# SOCL_506_GINDRING.net
KiCad netlist of a schematic drawn in EAGLE
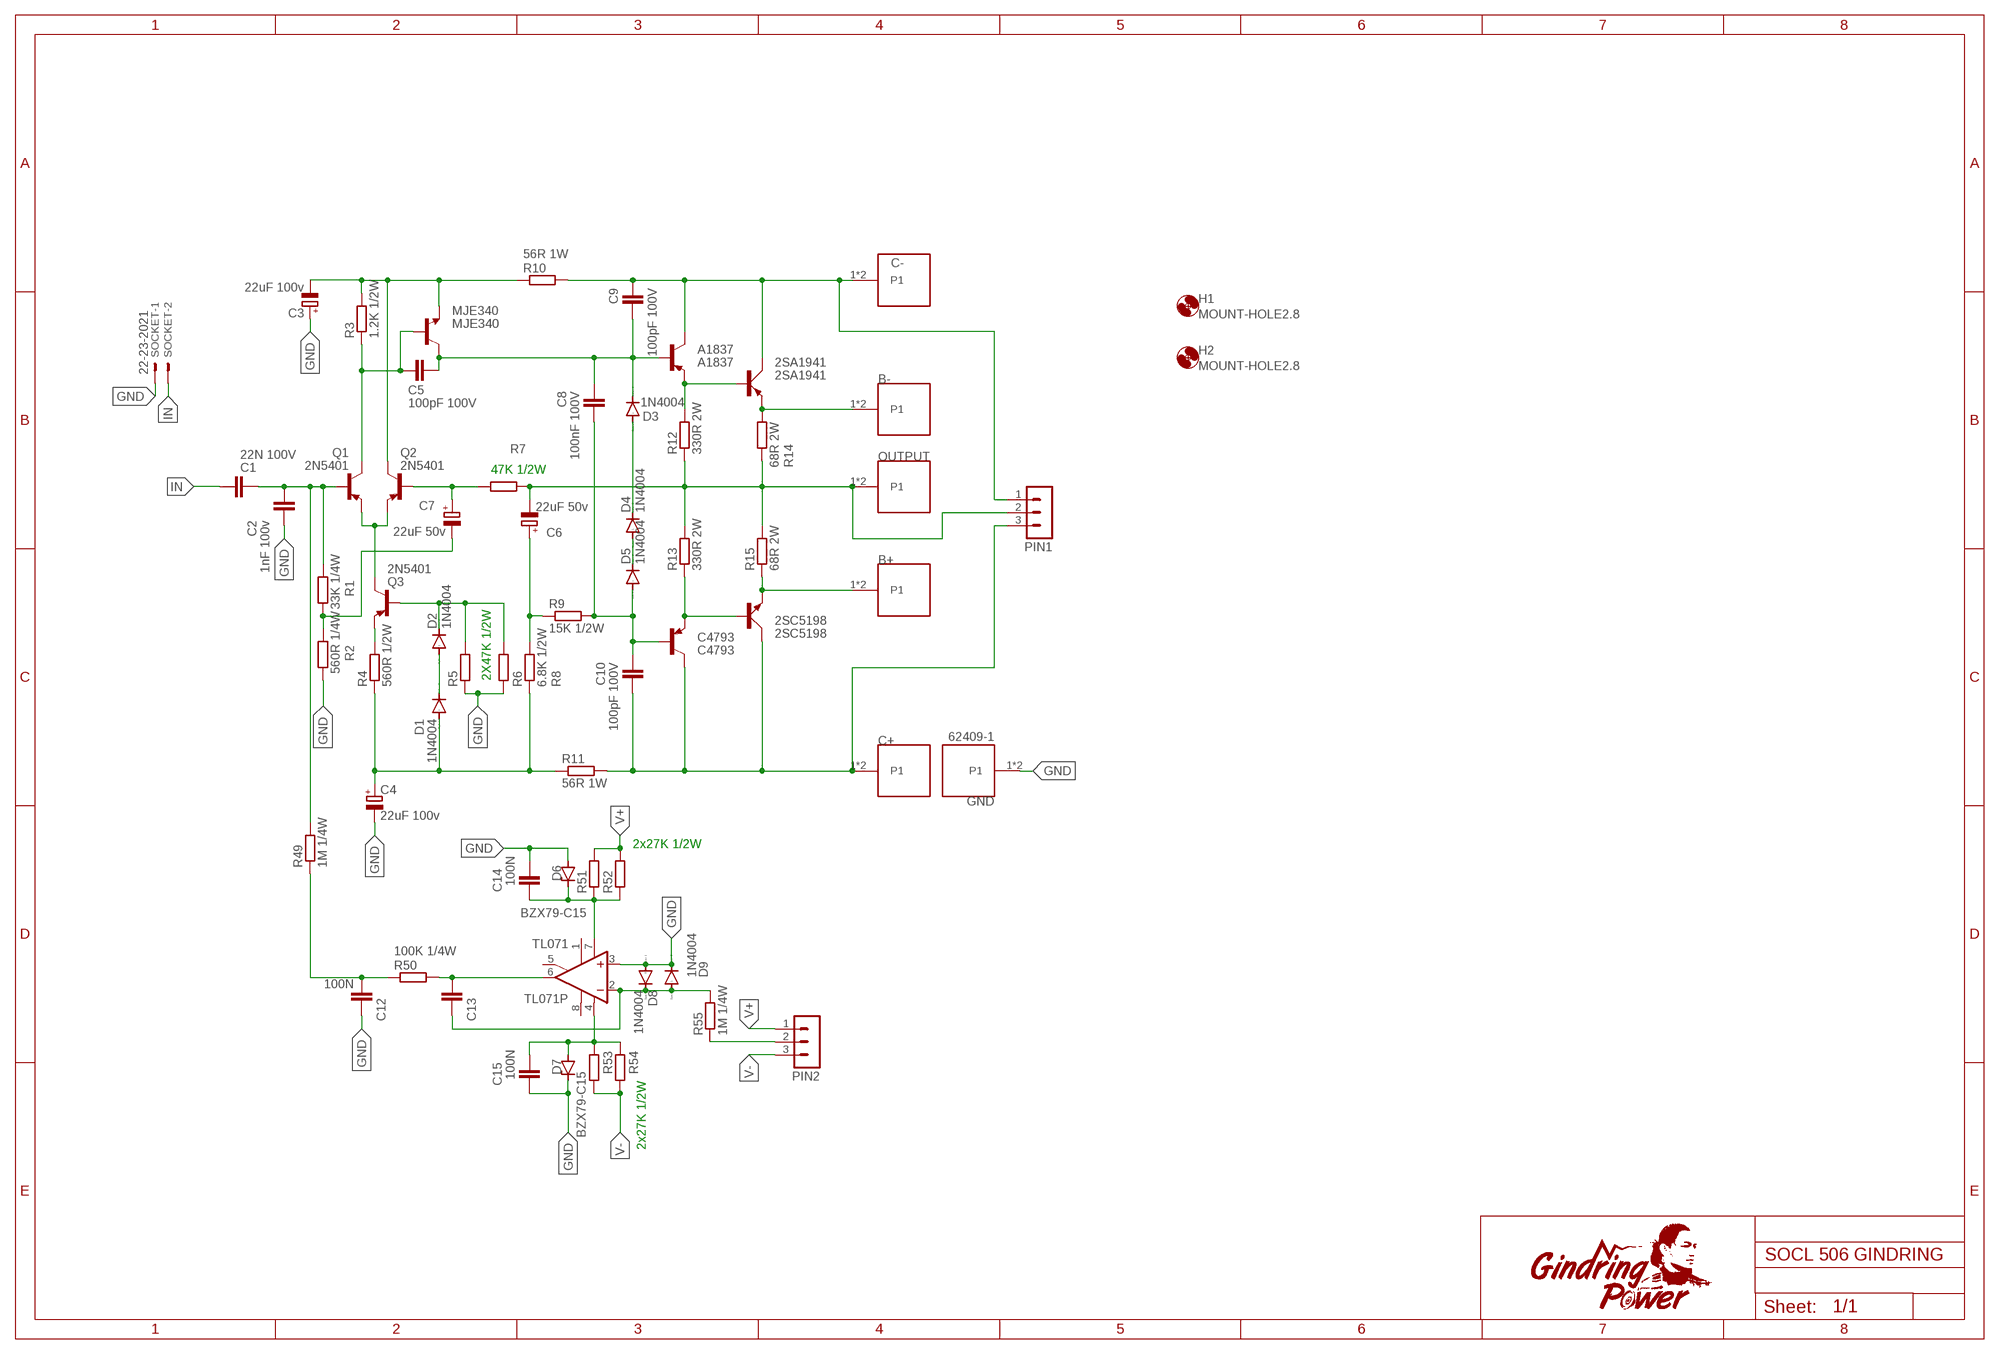
[diagram p0: schematic, sheet 1]

(export (version "E")
  (design (tool "Eeschema 10.0.6"))
  (components
    (comp (ref "2SA1941")
      (value "2SA1941")
      (footprint "eagle-import:TOP3AV")
      (libsource (lib "eagle-import") (part "TIP2955"))
    )
    (comp (ref "2SC5198")
      (value "2SC5198")
      (footprint "eagle-import:TOP3AV")
      (libsource (lib "eagle-import") (part "TIP3055"))
    )
    (comp (ref "A1837")
      (value "A1837")
      (footprint "eagle-import:TO220V")
      (fields (field (name "MF") "Toshiba Semiconductor") (field (name "MP") "2SA1837"))
      (libsource (lib "eagle-import") (part "2SA1837"))
    )
    (comp (ref "B+")
      (value "62409-1")
      (footprint "eagle-import:TE_62409-1")
      (fields (field (name "MF") "TE Connectivity"))
      (libsource (lib "eagle-import") (part "62409-1"))
    )
    (comp (ref "B-")
      (value "62409-1")
      (footprint "eagle-import:TE_62409-1")
      (fields (field (name "MF") "TE Connectivity"))
      (libsource (lib "eagle-import") (part "62409-1"))
    )
    (comp (ref "C+")
      (value "62409-1")
      (footprint "eagle-import:TE_62409-1")
      (fields (field (name "MF") "TE Connectivity"))
      (libsource (lib "eagle-import") (part "62409-1"))
    )
    (comp (ref "C-")
      (value "62409-1")
      (footprint "eagle-import:TE_62409-1")
      (fields (field (name "MF") "TE Connectivity"))
      (libsource (lib "eagle-import") (part "62409-1"))
    )
    (comp (ref "C1")
      (value "22N 100V")
      (footprint "eagle-import:C5B2.5")
      (libsource (lib "eagle-import") (part "C5/2.5"))
    )
    (comp (ref "C2")
      (value "1nF 100v")
      (footprint "eagle-import:C5B2.5")
      (libsource (lib "eagle-import") (part "C5/2.5"))
    )
    (comp (ref "C3")
      (value "22uF 100v")
      (footprint "eagle-import:E3,5-8")
      (libsource (lib "eagle-import") (part "CPOL-EUE3.5-8"))
    )
    (comp (ref "C4")
      (value "22uF 100v")
      (footprint "eagle-import:E3,5-8")
      (libsource (lib "eagle-import") (part "CPOL-EUE3.5-8"))
    )
    (comp (ref "C5")
      (value "100pF 100V")
      (footprint "eagle-import:C5B2.5")
      (libsource (lib "eagle-import") (part "C5/2.5"))
    )
    (comp (ref "C6")
      (value "22uF 50v")
      (footprint "eagle-import:E2,5-6E")
      (libsource (lib "eagle-import") (part "CPOL-EUE2,5-6E"))
    )
    (comp (ref "C7")
      (value "22uF 50v")
      (footprint "eagle-import:E2,5-6E")
      (libsource (lib "eagle-import") (part "CPOL-EUE2,5-6E"))
    )
    (comp (ref "C8")
      (value "100nF 100V")
      (footprint "eagle-import:C5B2.5")
      (libsource (lib "eagle-import") (part "C5/2.5"))
    )
    (comp (ref "C9")
      (value "100pF 100V")
      (footprint "eagle-import:C5B2.5")
      (libsource (lib "eagle-import") (part "C5/2.5"))
    )
    (comp (ref "C10")
      (value "100pF 100V")
      (footprint "eagle-import:C5B2.5")
      (libsource (lib "eagle-import") (part "C5/2.5"))
    )
    (comp (ref "C12")
      (value "100N")
      (footprint "eagle-import:C5B2.5")
      (libsource (lib "eagle-import") (part "C5/2.5"))
    )
    (comp (ref "C13")
      (value "100N")
      (footprint "eagle-import:C5B2.5")
      (libsource (lib "eagle-import") (part "C5/2.5"))
    )
    (comp (ref "C14")
      (value "100N")
      (footprint "eagle-import:C5B2.5")
      (libsource (lib "eagle-import") (part "C5/2.5"))
    )
    (comp (ref "C15")
      (value "100N")
      (footprint "eagle-import:C5B2.5")
      (libsource (lib "eagle-import") (part "C5/2.5"))
    )
    (comp (ref "C4793")
      (value "C4793")
      (footprint "eagle-import:TO220V")
      (fields (field (name "MF") "Toshiba Semiconductor") (field (name "MP") "2SA1837"))
      (libsource (lib "eagle-import") (part "2SA1837"))
    )
    (comp (ref "D1")
      (value "1N4004")
      (footprint "eagle-import:DO41-10")
      (libsource (lib "eagle-import") (part "1N4004"))
    )
    (comp (ref "D2")
      (value "1N4004")
      (footprint "eagle-import:DO41-10")
      (libsource (lib "eagle-import") (part "1N4004"))
    )
    (comp (ref "D3")
      (value "1N4004")
      (footprint "eagle-import:DO41-10")
      (libsource (lib "eagle-import") (part "1N4004"))
    )
    (comp (ref "D4")
      (value "1N4004")
      (footprint "eagle-import:DO41-10")
      (libsource (lib "eagle-import") (part "1N4004"))
    )
    (comp (ref "D5")
      (value "1N4004")
      (footprint "eagle-import:DO41-10")
      (libsource (lib "eagle-import") (part "1N4004"))
    )
    (comp (ref "D6")
      (value "BZX79-C15")
      (footprint "eagle-import:DO41Z10")
      (libsource (lib "eagle-import") (part "1N4728"))
    )
    (comp (ref "D7")
      (value "BZX79-C15")
      (footprint "eagle-import:DO41Z10")
      (libsource (lib "eagle-import") (part "1N4728"))
    )
    (comp (ref "D8")
      (value "1N4004")
      (footprint "eagle-import:DO41-10")
      (libsource (lib "eagle-import") (part "1N4004"))
    )
    (comp (ref "D9")
      (value "1N4004")
      (footprint "eagle-import:DO41-10")
      (libsource (lib "eagle-import") (part "1N4004"))
    )
    (comp (ref "GND")
      (value "62409-1")
      (footprint "eagle-import:TE_62409-1")
      (fields (field (name "MF") "TE Connectivity"))
      (libsource (lib "eagle-import") (part "62409-1"))
    )
    (comp (ref "H1")
      (value "MOUNT-HOLE2.8")
      (footprint "eagle-import:2,8")
      (libsource (lib "eagle-import") (part "MOUNT-HOLE2.8"))
    )
    (comp (ref "H2")
      (value "MOUNT-HOLE2.8")
      (footprint "eagle-import:2,8")
      (libsource (lib "eagle-import") (part "MOUNT-HOLE2.8"))
    )
    (comp (ref "MJE340")
      (value "MJE340")
      (footprint "eagle-import:TO126")
      (fields (field (name "MF") "STMicroelectronics"))
      (libsource (lib "eagle-import") (part "MJE340"))
    )
    (comp (ref "OUTPUT")
      (value "62409-1")
      (footprint "eagle-import:TE_62409-1")
      (fields (field (name "MF") "TE Connectivity"))
      (libsource (lib "eagle-import") (part "62409-1"))
    )
    (comp (ref "PIN1")
      (value "MA03-1")
      (footprint "eagle-import:MA03-1")
      (libsource (lib "eagle-import") (part "MA03-1"))
    )
    (comp (ref "PIN2")
      (value "MA03-1")
      (footprint "eagle-import:MA03-1")
      (libsource (lib "eagle-import") (part "MA03-1"))
    )
    (comp (ref "Q1")
      (value "2N5401")
      (footprint "eagle-import:TO92-CBE")
      (libsource (lib "eagle-import") (part "-?TO92MPSA56"))
    )
    (comp (ref "Q2")
      (value "2N5401")
      (footprint "eagle-import:TO92-CBE")
      (libsource (lib "eagle-import") (part "-?TO92MPSA56"))
    )
    (comp (ref "Q3")
      (value "2N5401")
      (footprint "eagle-import:TO92-CBE")
      (libsource (lib "eagle-import") (part "-?TO92MPSA56"))
    )
    (comp (ref "R1")
      (value "33K 1/4W")
      (footprint "eagle-import:0207_10")
      (libsource (lib "eagle-import") (part "R-EU_0207/10"))
    )
    (comp (ref "R2")
      (value "560R 1/4W")
      (footprint "eagle-import:0207_10")
      (libsource (lib "eagle-import") (part "R-EU_0207/10"))
    )
    (comp (ref "R3")
      (value "1.2K 1/2W")
      (footprint "eagle-import:0207_15")
      (libsource (lib "eagle-import") (part "resistor coba_R-EU_0207/15"))
    )
    (comp (ref "R4")
      (value "560R 1/2W")
      (footprint "eagle-import:0207_15")
      (libsource (lib "eagle-import") (part "resistor coba_R-EU_0207/15"))
    )
    (comp (ref "R5")
      (value "R-EU_0207/15")
      (footprint "eagle-import:0207_15")
      (libsource (lib "eagle-import") (part "resistor coba_R-EU_0207/15"))
    )
    (comp (ref "R6")
      (value "R-EU_0207/15")
      (footprint "eagle-import:0207_15")
      (libsource (lib "eagle-import") (part "resistor coba_R-EU_0207/15"))
    )
    (comp (ref "R7")
      (value "R-EU_0207/15")
      (footprint "eagle-import:0207_15")
      (libsource (lib "eagle-import") (part "resistor coba_R-EU_0207/15"))
    )
    (comp (ref "R8")
      (value "6.8K 1/2W")
      (footprint "eagle-import:0207_15")
      (libsource (lib "eagle-import") (part "resistor coba_R-EU_0207/15"))
    )
    (comp (ref "R9")
      (value "15K 1/2W")
      (footprint "eagle-import:0207_15")
      (libsource (lib "eagle-import") (part "resistor coba_R-EU_0207/15"))
    )
    (comp (ref "R10")
      (value "56R 1W")
      (footprint "eagle-import:0207_15")
      (libsource (lib "eagle-import") (part "resistor coba_R-EU_0207/15"))
    )
    (comp (ref "R11")
      (value "56R 1W")
      (footprint "eagle-import:0207_15")
      (libsource (lib "eagle-import") (part "resistor coba_R-EU_0207/15"))
    )
    (comp (ref "R12")
      (value "330R 2W")
      (footprint "eagle-import:0207_15")
      (libsource (lib "eagle-import") (part "resistor coba_R-EU_0207/15"))
    )
    (comp (ref "R13")
      (value "330R 2W")
      (footprint "eagle-import:0207_15")
      (libsource (lib "eagle-import") (part "resistor coba_R-EU_0207/15"))
    )
    (comp (ref "R14")
      (value "68R 2W")
      (footprint "eagle-import:0207_15")
      (libsource (lib "eagle-import") (part "resistor coba_R-EU_0207/15"))
    )
    (comp (ref "R15")
      (value "68R 2W")
      (footprint "eagle-import:0207_15")
      (libsource (lib "eagle-import") (part "resistor coba_R-EU_0207/15"))
    )
    (comp (ref "R49")
      (value "1M 1/4W")
      (footprint "eagle-import:0207_10")
      (libsource (lib "eagle-import") (part "R-EU_0207/10"))
    )
    (comp (ref "R50")
      (value "100K 1/4W")
      (footprint "eagle-import:0207_10")
      (libsource (lib "eagle-import") (part "R-EU_0207/10"))
    )
    (comp (ref "R51")
      (value "R-EU_0207/15")
      (footprint "eagle-import:0207_15")
      (libsource (lib "eagle-import") (part "resistor coba_R-EU_0207/15"))
    )
    (comp (ref "R52")
      (value "R-EU_0207/15")
      (footprint "eagle-import:0207_15")
      (libsource (lib "eagle-import") (part "resistor coba_R-EU_0207/15"))
    )
    (comp (ref "R53")
      (value "R-EU_0207/15")
      (footprint "eagle-import:0207_15")
      (libsource (lib "eagle-import") (part "resistor coba_R-EU_0207/15"))
    )
    (comp (ref "R54")
      (value "R-EU_0207/15")
      (footprint "eagle-import:0207_15")
      (libsource (lib "eagle-import") (part "resistor coba_R-EU_0207/15"))
    )
    (comp (ref "R55")
      (value "1M 1/4W")
      (footprint "eagle-import:0207_10")
      (libsource (lib "eagle-import") (part "R-EU_0207/10"))
    )
    (comp (ref "SOCKET")
      (value "22-23-2021")
      (footprint "eagle-import:22-23-2021")
      (fields (field (name "MF") "MOLEX"))
      (libsource (lib "eagle-import") (part "22-23-2021"))
    )
    (comp (ref "TL071")
      (value "TL071P")
      (footprint "eagle-import:DIL08")
      (fields (field (name "MF") "STMicroelectronics") (field (name "MP") "TL071"))
      (libsource (lib "eagle-import") (part "TL071P"))
    )
  )
  (nets
    (net (code "1") (name "GND") (class "Default")
      (node (ref "C12") (pin "1") (pinfunction "1_1") (pintype "passive"))
      (node (ref "C14") (pin "2") (pinfunction "2_2") (pintype "passive"))
      (node (ref "C15") (pin "1") (pinfunction "1_1") (pintype "passive"))
      (node (ref "C2") (pin "2") (pinfunction "2_2") (pintype "passive"))
      (node (ref "C3") (pin "+") (pinfunction "+_+") (pintype "passive"))
      (node (ref "C4") (pin "-") (pinfunction "-_-") (pintype "passive"))
      (node (ref "D6") (pin "A") (pinfunction "A_A") (pintype "passive"))
      (node (ref "D7") (pin "C") (pinfunction "C_C") (pintype "passive"))
      (node (ref "D8") (pin "A") (pinfunction "A_A") (pintype "passive"))
      (node (ref "D9") (pin "C") (pinfunction "C_C") (pintype "passive"))
      (node (ref "GND") (pin "1") (pinfunction "P1_1") (pintype "passive"))
      (node (ref "GND") (pin "2") (pinfunction "P1_2") (pintype "passive"))
      (node (ref "R2") (pin "1") (pinfunction "1_1") (pintype "passive"))
      (node (ref "R5") (pin "1") (pinfunction "1_1") (pintype "passive"))
      (node (ref "R6") (pin "1") (pinfunction "1_1") (pintype "passive"))
      (node (ref "SOCKET") (pin "1") (pinfunction "S_1") (pintype "passive"))
      (node (ref "TL071") (pin "3") (pinfunction "+IN_3") (pintype "input"))
    )
    (net (code "2") (name "IN") (class "Default")
      (node (ref "C1") (pin "1") (pinfunction "1_1") (pintype "passive"))
      (node (ref "SOCKET") (pin "2") (pinfunction "S_2") (pintype "passive"))
    )
    (net (code "3") (name "Net-(2SA1941-PadE)") (class "Default")
      (node (ref "2SA1941") (pin "E") (pinfunction "E_E") (pintype "passive"))
      (node (ref "B-") (pin "1") (pinfunction "P1_1") (pintype "passive"))
      (node (ref "B-") (pin "2") (pinfunction "P1_2") (pintype "passive"))
      (node (ref "R14") (pin "2") (pinfunction "2_2") (pintype "passive"))
    )
    (net (code "4") (name "Net-(2SC5198-PadE)") (class "Default")
      (node (ref "2SC5198") (pin "E") (pinfunction "E_E") (pintype "passive"))
      (node (ref "B+") (pin "1") (pinfunction "P1_1") (pintype "passive"))
      (node (ref "B+") (pin "2") (pinfunction "P1_2") (pintype "passive"))
      (node (ref "R15") (pin "1") (pinfunction "1_1") (pintype "passive"))
    )
    (net (code "5") (name "Net-(A1837-B)") (class "Default")
      (node (ref "A1837") (pin "1") (pinfunction "B_1") (pintype "passive"))
      (node (ref "C5") (pin "2") (pinfunction "2_2") (pintype "passive"))
      (node (ref "C8") (pin "2") (pinfunction "2_2") (pintype "passive"))
      (node (ref "C9") (pin "1") (pinfunction "1_1") (pintype "passive"))
      (node (ref "D3") (pin "C") (pinfunction "C_C") (pintype "passive"))
      (node (ref "MJE340") (pin "2") (pinfunction "C_2") (pintype "passive"))
    )
    (net (code "6") (name "Net-(A1837-C)") (class "Default")
      (node (ref "2SA1941") (pin "C") (pinfunction "C_C") (pintype "passive"))
      (node (ref "A1837") (pin "2") (pinfunction "C_2") (pintype "passive"))
      (node (ref "C-") (pin "1") (pinfunction "P1_1") (pintype "passive"))
      (node (ref "C-") (pin "2") (pinfunction "P1_2") (pintype "passive"))
      (node (ref "C9") (pin "2") (pinfunction "2_2") (pintype "passive"))
      (node (ref "PIN1") (pin "1") (pinfunction "1_1") (pintype "passive"))
      (node (ref "R10") (pin "2") (pinfunction "2_2") (pintype "passive"))
    )
    (net (code "7") (name "Net-(A1837-E)") (class "Default")
      (node (ref "2SA1941") (pin "B") (pinfunction "B_B") (pintype "passive"))
      (node (ref "A1837") (pin "3") (pinfunction "E_3") (pintype "passive"))
      (node (ref "R12") (pin "2") (pinfunction "2_2") (pintype "passive"))
    )
    (net (code "8") (name "Net-(C1-Pad2)") (class "Default")
      (node (ref "C1") (pin "2") (pinfunction "2_2") (pintype "passive"))
      (node (ref "C2") (pin "1") (pinfunction "1_1") (pintype "passive"))
      (node (ref "Q1") (pin "B") (pinfunction "B_B") (pintype "passive"))
      (node (ref "R1") (pin "2") (pinfunction "2_2") (pintype "passive"))
      (node (ref "R49") (pin "2") (pinfunction "2_2") (pintype "passive"))
    )
    (net (code "9") (name "Net-(C4-Pad+)") (class "Default")
      (node (ref "C4") (pin "+") (pinfunction "+_+") (pintype "passive"))
      (node (ref "D1") (pin "A") (pinfunction "A_A") (pintype "passive"))
      (node (ref "R11") (pin "1") (pinfunction "1_1") (pintype "passive"))
      (node (ref "R4") (pin "1") (pinfunction "1_1") (pintype "passive"))
      (node (ref "R8") (pin "1") (pinfunction "1_1") (pintype "passive"))
    )
    (net (code "10") (name "Net-(C6-Pad+)") (class "Default")
      (node (ref "C6") (pin "+") (pinfunction "+_+") (pintype "passive"))
      (node (ref "R8") (pin "2") (pinfunction "2_2") (pintype "passive"))
      (node (ref "R9") (pin "1") (pinfunction "1_1") (pintype "passive"))
    )
    (net (code "11") (name "Net-(C6-Pad-)") (class "Default")
      (node (ref "C6") (pin "-") (pinfunction "-_-") (pintype "passive"))
      (node (ref "OUTPUT") (pin "1") (pinfunction "P1_1") (pintype "passive"))
      (node (ref "OUTPUT") (pin "2") (pinfunction "P1_2") (pintype "passive"))
      (node (ref "PIN1") (pin "2") (pinfunction "2_2") (pintype "passive"))
      (node (ref "R12") (pin "1") (pinfunction "1_1") (pintype "passive"))
      (node (ref "R13") (pin "2") (pinfunction "2_2") (pintype "passive"))
      (node (ref "R14") (pin "1") (pinfunction "1_1") (pintype "passive"))
      (node (ref "R15") (pin "2") (pinfunction "2_2") (pintype "passive"))
      (node (ref "R7") (pin "2") (pinfunction "2_2") (pintype "passive"))
    )
    (net (code "12") (name "Net-(C7-Pad+)") (class "Default")
      (node (ref "C7") (pin "+") (pinfunction "+_+") (pintype "passive"))
      (node (ref "Q2") (pin "B") (pinfunction "B_B") (pintype "passive"))
      (node (ref "R7") (pin "1") (pinfunction "1_1") (pintype "passive"))
    )
    (net (code "13") (name "Net-(C7-Pad-)") (class "Default")
      (node (ref "C7") (pin "-") (pinfunction "-_-") (pintype "passive"))
      (node (ref "R1") (pin "1") (pinfunction "1_1") (pintype "passive"))
      (node (ref "R2") (pin "2") (pinfunction "2_2") (pintype "passive"))
    )
    (net (code "14") (name "Net-(C12-Pad2)") (class "Default")
      (node (ref "C12") (pin "2") (pinfunction "2_2") (pintype "passive"))
      (node (ref "R49") (pin "1") (pinfunction "1_1") (pintype "passive"))
      (node (ref "R50") (pin "1") (pinfunction "1_1") (pintype "passive"))
    )
    (net (code "15") (name "Net-(C4793-B)") (class "Default")
      (node (ref "C10") (pin "2") (pinfunction "2_2") (pintype "passive"))
      (node (ref "C4793") (pin "1") (pinfunction "B_1") (pintype "passive"))
      (node (ref "C8") (pin "1") (pinfunction "1_1") (pintype "passive"))
      (node (ref "D5") (pin "A") (pinfunction "A_A") (pintype "passive"))
      (node (ref "R9") (pin "2") (pinfunction "2_2") (pintype "passive"))
    )
    (net (code "16") (name "Net-(C4793-C)") (class "Default")
      (node (ref "2SC5198") (pin "C") (pinfunction "C_C") (pintype "passive"))
      (node (ref "C+") (pin "1") (pinfunction "P1_1") (pintype "passive"))
      (node (ref "C+") (pin "2") (pinfunction "P1_2") (pintype "passive"))
      (node (ref "C10") (pin "1") (pinfunction "1_1") (pintype "passive"))
      (node (ref "C4793") (pin "2") (pinfunction "C_2") (pintype "passive"))
      (node (ref "PIN1") (pin "3") (pinfunction "3_3") (pintype "passive"))
      (node (ref "R11") (pin "2") (pinfunction "2_2") (pintype "passive"))
    )
    (net (code "17") (name "Net-(C4793-E)") (class "Default")
      (node (ref "2SC5198") (pin "B") (pinfunction "B_B") (pintype "passive"))
      (node (ref "C4793") (pin "3") (pinfunction "E_3") (pintype "passive"))
      (node (ref "R13") (pin "1") (pinfunction "1_1") (pintype "passive"))
    )
    (net (code "18") (name "Net-(D1-PadC)") (class "Default")
      (node (ref "D1") (pin "C") (pinfunction "C_C") (pintype "passive"))
      (node (ref "D2") (pin "A") (pinfunction "A_A") (pintype "passive"))
    )
    (net (code "19") (name "Net-(D2-PadC)") (class "Default")
      (node (ref "D2") (pin "C") (pinfunction "C_C") (pintype "passive"))
      (node (ref "Q3") (pin "B") (pinfunction "B_B") (pintype "passive"))
      (node (ref "R5") (pin "2") (pinfunction "2_2") (pintype "passive"))
      (node (ref "R6") (pin "2") (pinfunction "2_2") (pintype "passive"))
    )
    (net (code "20") (name "Net-(D3-PadA)") (class "Default")
      (node (ref "D3") (pin "A") (pinfunction "A_A") (pintype "passive"))
      (node (ref "D4") (pin "C") (pinfunction "C_C") (pintype "passive"))
    )
    (net (code "21") (name "Net-(D4-PadA)") (class "Default")
      (node (ref "D4") (pin "A") (pinfunction "A_A") (pintype "passive"))
      (node (ref "D5") (pin "C") (pinfunction "C_C") (pintype "passive"))
    )
    (net (code "22") (name "Net-(MJE340-B)") (class "Default")
      (node (ref "C5") (pin "1") (pinfunction "1_1") (pintype "passive"))
      (node (ref "MJE340") (pin "3") (pinfunction "B_3") (pintype "passive"))
      (node (ref "Q1") (pin "C") (pinfunction "C_C") (pintype "passive"))
      (node (ref "R3") (pin "1") (pinfunction "1_1") (pintype "passive"))
    )
    (net (code "23") (name "Net-(MJE340-E)") (class "Default")
      (node (ref "C3") (pin "-") (pinfunction "-_-") (pintype "passive"))
      (node (ref "MJE340") (pin "1") (pinfunction "E_1") (pintype "passive"))
      (node (ref "Q2") (pin "C") (pinfunction "C_C") (pintype "passive"))
      (node (ref "R10") (pin "1") (pinfunction "1_1") (pintype "passive"))
      (node (ref "R3") (pin "2") (pinfunction "2_2") (pintype "passive"))
    )
    (net (code "24") (name "Net-(PIN2-Pad2)") (class "Default")
      (node (ref "PIN2") (pin "2") (pinfunction "2_2") (pintype "passive"))
      (node (ref "R55") (pin "1") (pinfunction "1_1") (pintype "passive"))
    )
    (net (code "25") (name "Net-(Q1-PadE)") (class "Default")
      (node (ref "Q1") (pin "E") (pinfunction "E_E") (pintype "passive"))
      (node (ref "Q2") (pin "E") (pinfunction "E_E") (pintype "passive"))
      (node (ref "Q3") (pin "C") (pinfunction "C_C") (pintype "passive"))
    )
    (net (code "26") (name "Net-(Q3-PadE)") (class "Default")
      (node (ref "Q3") (pin "E") (pinfunction "E_E") (pintype "passive"))
      (node (ref "R4") (pin "2") (pinfunction "2_2") (pintype "passive"))
    )
    (net (code "27") (name "Net-(TL071--IN)") (class "Default")
      (node (ref "C13") (pin "1") (pinfunction "1_1") (pintype "passive"))
      (node (ref "D8") (pin "C") (pinfunction "C_C") (pintype "passive"))
      (node (ref "D9") (pin "A") (pinfunction "A_A") (pintype "passive"))
      (node (ref "R55") (pin "2") (pinfunction "2_2") (pintype "passive"))
      (node (ref "TL071") (pin "2") (pinfunction "-IN_2") (pintype "input"))
    )
    (net (code "28") (name "Net-(TL071-OUT)") (class "Default")
      (node (ref "C13") (pin "2") (pinfunction "2_2") (pintype "passive"))
      (node (ref "R50") (pin "2") (pinfunction "2_2") (pintype "passive"))
      (node (ref "TL071") (pin "6") (pinfunction "OUT_6") (pintype "output"))
    )
    (net (code "29") (name "Net-(TL071-V+)") (class "Default")
      (node (ref "C14") (pin "1") (pinfunction "1_1") (pintype "passive"))
      (node (ref "D6") (pin "C") (pinfunction "C_C") (pintype "passive"))
      (node (ref "R51") (pin "1") (pinfunction "1_1") (pintype "passive"))
      (node (ref "R52") (pin "1") (pinfunction "1_1") (pintype "passive"))
      (node (ref "TL071") (pin "7") (pinfunction "V+_7") (pintype "power_in"))
    )
    (net (code "30") (name "Net-(TL071-V-)") (class "Default")
      (node (ref "C15") (pin "2") (pinfunction "2_2") (pintype "passive"))
      (node (ref "D7") (pin "A") (pinfunction "A_A") (pintype "passive"))
      (node (ref "R53") (pin "2") (pinfunction "2_2") (pintype "passive"))
      (node (ref "R54") (pin "2") (pinfunction "2_2") (pintype "passive"))
      (node (ref "TL071") (pin "4") (pinfunction "V-_4") (pintype "power_in"))
    )
    (net (code "31") (name "V+") (class "Default")
      (node (ref "PIN2") (pin "1") (pinfunction "1_1") (pintype "passive"))
      (node (ref "R51") (pin "2") (pinfunction "2_2") (pintype "passive"))
      (node (ref "R52") (pin "2") (pinfunction "2_2") (pintype "passive"))
    )
    (net (code "32") (name "V-") (class "Default")
      (node (ref "PIN2") (pin "3") (pinfunction "3_3") (pintype "passive"))
      (node (ref "R53") (pin "1") (pinfunction "1_1") (pintype "passive"))
      (node (ref "R54") (pin "1") (pinfunction "1_1") (pintype "passive"))
    )
    (net (code "33") (name "unconnected-(TL071-ON1-Pad1)") (class "Default")
      (node (ref "TL071") (pin "1") (pinfunction "ON1_1") (pintype "passive"))
    )
    (net (code "34") (name "unconnected-(TL071-ON2-Pad5)") (class "Default")
      (node (ref "TL071") (pin "5") (pinfunction "ON2_5") (pintype "passive"))
    )
    (net (code "35") (name "unconnected-(TL071-OPT-Pad8)") (class "Default")
      (node (ref "TL071") (pin "8") (pinfunction "OPT_8") (pintype "passive"))
    )
  )
)
